# Miscel.net
KiCad netlist of a schematic drawn in EasyEDA
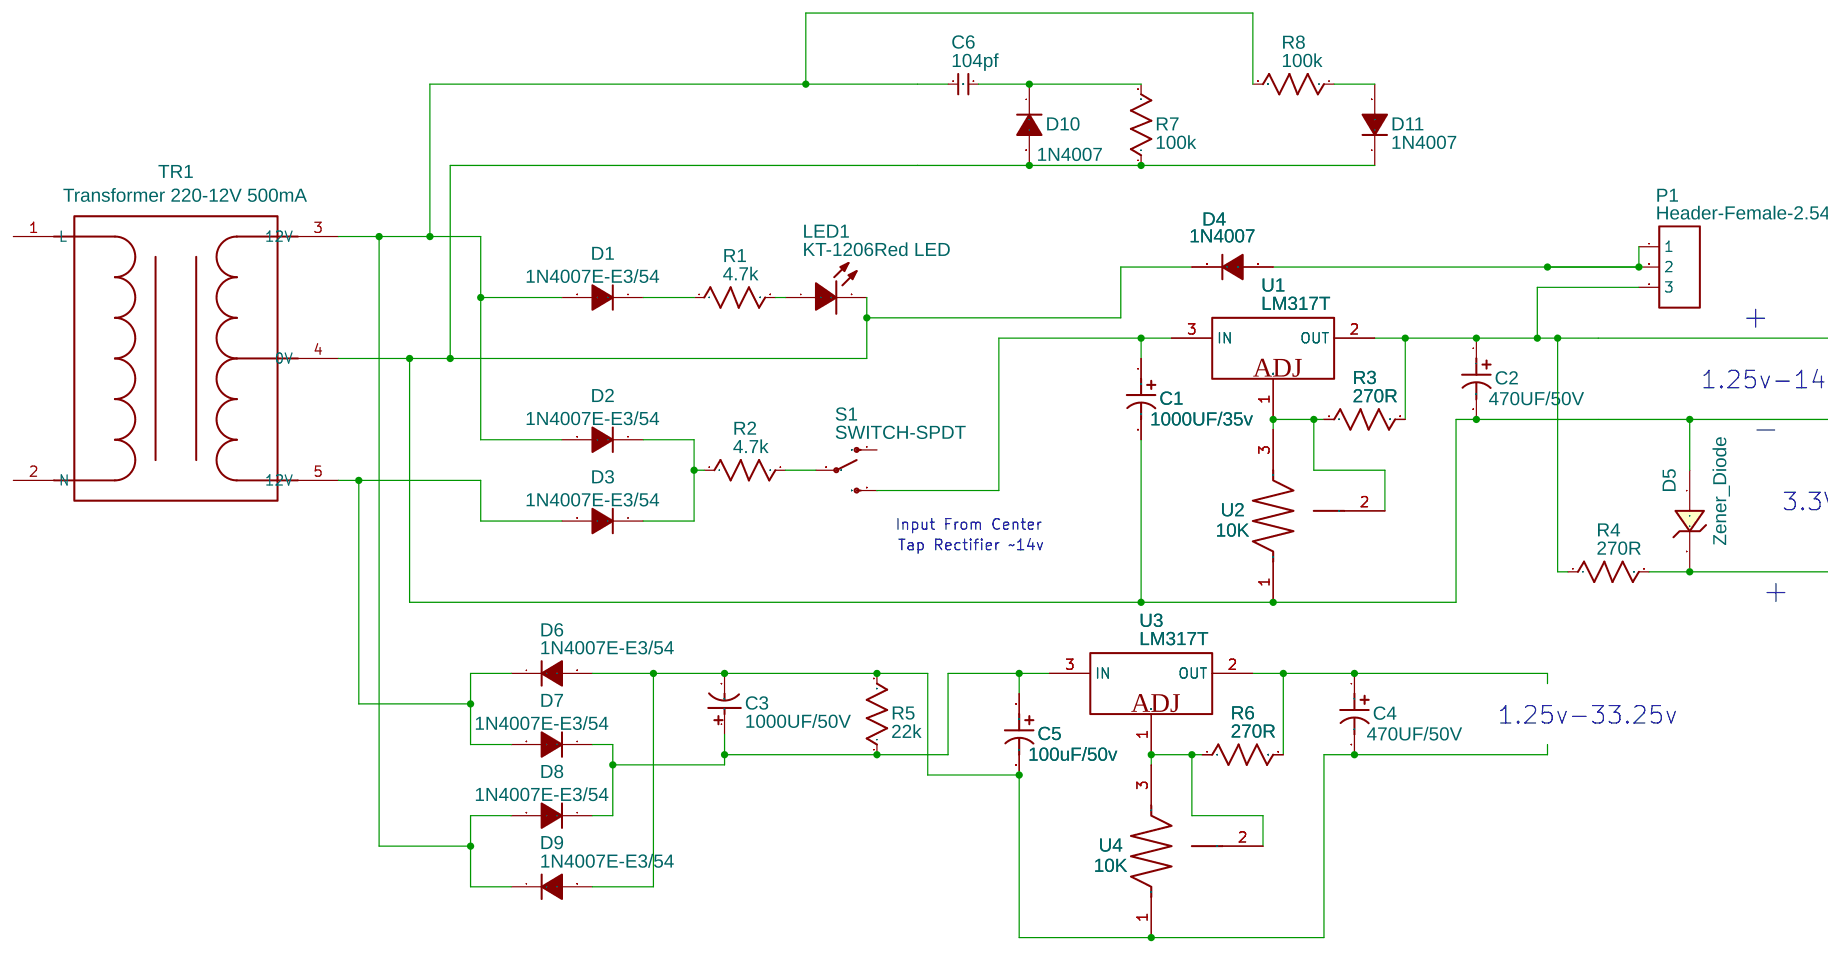
[diagram p0: schematic sheet]

(export (version "E")
  (design (tool "Eeschema 10.0.6"))
  (components
    (comp (ref "C1")
      (value "1000UF/35v")
      (fields
        (field (name "BOM_Manufacturer Part") "100uF/50V")
        (field (name "BOM_Supplier Part") "C9900004739")
      )
      (libsource (lib "") (part "100UF/50V"))
    )
    (comp (ref "C2")
      (value "470UF/50V")
      (fields
        (field (name "BOM_Manufacturer Part") "470uF/50V-10x20")
        (field (name "BOM_Supplier Part") "C9900005233")
      )
      (libsource (lib "") (part "470UF/50V-10X20"))
    )
    (comp (ref "C3")
      (value "1000UF/50V")
      (fields
        (field (name "BOM_Manufacturer Part") "1000uF/50V")
        (field (name "BOM_Supplier Part") "C9900023728")
      )
      (libsource (lib "") (part "1000UF/50V"))
    )
    (comp (ref "C4")
      (value "470UF/50V")
      (fields
        (field (name "BOM_Manufacturer Part") "470uF/50V-10x20")
        (field (name "BOM_Supplier Part") "C9900005233")
      )
      (libsource (lib "") (part "470UF/50V-10X20"))
    )
    (comp (ref "C5")
      (value "100uF/50v")
      (fields
        (field (name "BOM_Manufacturer Part") "100uF/50V")
        (field (name "BOM_Supplier Part") "C9900004739")
      )
      (libsource (lib "") (part "100UF/50V"))
    )
    (comp (ref "C6") (value "104pf") (libsource (lib "") (part "104pf")))
    (comp (ref "D1")
      (value "1N4007E-E3/54")
      (fields (field (name "BOM_Supplier Part") "C144970"))
      (libsource (lib "") (part "1N4007E-E3/54"))
    )
    (comp (ref "D2")
      (value "1N4007E-E3/54")
      (fields (field (name "BOM_Supplier Part") "C144970"))
      (libsource (lib "") (part "1N4007E-E3/54"))
    )
    (comp (ref "D3")
      (value "1N4007E-E3/54")
      (fields (field (name "BOM_Supplier Part") "C144970"))
      (libsource (lib "") (part "1N4007E-E3/54"))
    )
    (comp (ref "D4")
      (value "1N4007")
      (fields
        (field (name "BOM_Manufacturer Part") "1N4007E-E3/54")
        (field (name "BOM_Supplier Part") "C144970")
      )
      (libsource (lib "") (part "1N4007E-E3/54_2"))
    )
    (comp (ref "D5") (value "Zener_Diode") (libsource (lib "") (part "Zener_Diode")))
    (comp (ref "D6")
      (value "1N4007E-E3/54")
      (fields (field (name "BOM_Supplier Part") "C144970"))
      (libsource (lib "") (part "1N4007E-E3/54_2"))
    )
    (comp (ref "D7")
      (value "1N4007E-E3/54")
      (fields (field (name "BOM_Supplier Part") "C144970"))
      (libsource (lib "") (part "1N4007E-E3/54"))
    )
    (comp (ref "D8")
      (value "1N4007E-E3/54")
      (fields (field (name "BOM_Supplier Part") "C144970"))
      (libsource (lib "") (part "1N4007E-E3/54"))
    )
    (comp (ref "D9")
      (value "1N4007E-E3/54")
      (fields (field (name "BOM_Supplier Part") "C144970"))
      (libsource (lib "") (part "1N4007E-E3/54_2"))
    )
    (comp (ref "D10")
      (value "1N4007")
      (fields
        (field (name "BOM_Manufacturer Part") "1N4007E-E3/54")
        (field (name "BOM_Supplier Part") "C144970")
      )
      (libsource (lib "") (part "1N4007E-E3/54_3"))
    )
    (comp (ref "D11")
      (value "1N4007")
      (fields
        (field (name "BOM_Manufacturer Part") "1N4007E-E3/54")
        (field (name "BOM_Supplier Part") "C144970")
      )
      (libsource (lib "") (part "1N4007E-E3/54_1"))
    )
    (comp (ref "LED1")
      (value "KT-1206Red LED")
      (fields (field (name "BOM_Supplier Part") "C49018"))
      (libsource (lib "") (part "KT-1206Red LED"))
    )
    (comp (ref "P1")
      (value "Header-Female-2.54_1x3")
      (fields
        (field (name "BOM_Manufacturer Part") "2.54-1*3P母")
        (field (name "BOM_Supplier Part") "C146243")
      )
      (libsource (lib "") (part "Header-Female-2.54_1x3"))
    )
    (comp (ref "R1") (value "4.7k") (libsource (lib "") (part "R_0603_US")))
    (comp (ref "R2") (value "4.7k") (libsource (lib "") (part "R_0603_US")))
    (comp (ref "R3") (value "270R") (libsource (lib "") (part "R_0603_US")))
    (comp (ref "R4") (value "270R") (libsource (lib "") (part "R_0603_US")))
    (comp (ref "R5") (value "22k") (libsource (lib "") (part "R_0603_US_1")))
    (comp (ref "R6") (value "270R") (libsource (lib "") (part "R_0603_US")))
    (comp (ref "R7") (value "100k") (libsource (lib "") (part "R_0603_US_1")))
    (comp (ref "R8") (value "100k") (libsource (lib "") (part "R_0603_US_2")))
    (comp (ref "S1") (value "SWITCH-SPDT") (libsource (lib "") (part "SWITCH-SPDT")))
    (comp (ref "TR1")
      (value "Transformer 220-12V 500mA")
      (libsource (lib "") (part "Transformer 220-12V 500mA"))
    )
    (comp (ref "U1") (value "LM317T") (libsource (lib "") (part "LM317T")))
    (comp (ref "U2") (value "10K") (libsource (lib "") (part "POTENTIOMETER")))
    (comp (ref "U3") (value "LM317T") (libsource (lib "") (part "LM317T")))
    (comp (ref "U4") (value "10K") (libsource (lib "") (part "POTENTIOMETER")))
  )
  (nets
    (net (code "1") (name "Net-(D1-A)") (class "Default")
      (node (ref "C6") (pin "1") (pinfunction "1_1") (pintype "unspecified"))
      (node (ref "D1") (pin "2") (pinfunction "A_2") (pintype "unspecified"))
      (node (ref "D2") (pin "2") (pinfunction "A_2") (pintype "unspecified"))
      (node (ref "D8") (pin "2") (pinfunction "A_2") (pintype "unspecified"))
      (node (ref "D9") (pin "1") (pinfunction "K_1") (pintype "unspecified"))
      (node (ref "R8") (pin "2") (pinfunction "2_2") (pintype "unspecified"))
      (node (ref "TR1") (pin "3") (pinfunction "12V_3") (pintype "unspecified"))
    )
    (net (code "2") (name "Net-(D1-K)") (class "Default")
      (node (ref "D1") (pin "1") (pinfunction "K_1") (pintype "unspecified"))
      (node (ref "R1") (pin "1") (pinfunction "1_1") (pintype "unspecified"))
    )
    (net (code "3") (name "Net-(D2-K)") (class "Default")
      (node (ref "D2") (pin "1") (pinfunction "K_1") (pintype "unspecified"))
      (node (ref "D3") (pin "1") (pinfunction "K_1") (pintype "unspecified"))
      (node (ref "R2") (pin "1") (pinfunction "1_1") (pintype "unspecified"))
    )
    (net (code "4") (name "Net-(D3-A)") (class "Default")
      (node (ref "D3") (pin "2") (pinfunction "A_2") (pintype "unspecified"))
      (node (ref "D6") (pin "1") (pinfunction "K_1") (pintype "unspecified"))
      (node (ref "D7") (pin "2") (pinfunction "A_2") (pintype "unspecified"))
      (node (ref "TR1") (pin "5") (pinfunction "12V_5") (pintype "unspecified"))
    )
    (net (code "5") (name "Net-(D4-A)") (class "Default")
      (node (ref "D4") (pin "2") (pinfunction "A_2") (pintype "unspecified"))
      (node (ref "P1") (pin "1") (pinfunction "1_1") (pintype "input"))
      (node (ref "P1") (pin "2") (pinfunction "2_2") (pintype "input"))
    )
    (net (code "6") (name "Net-(D5-K)") (class "Default")
      (node (ref "D5") (pin "2") (pinfunction "K_2") (pintype "unspecified"))
      (node (ref "R4") (pin "2") (pinfunction "2_2") (pintype "unspecified"))
    )
    (net (code "7") (name "Net-(D6-A)") (class "Default")
      (node (ref "C3") (pin "2") (pinfunction "2_2") (pintype "input"))
      (node (ref "C4") (pin "2") (pinfunction "2_2") (pintype "input"))
      (node (ref "C5") (pin "2") (pinfunction "2_2") (pintype "input"))
      (node (ref "D6") (pin "2") (pinfunction "A_2") (pintype "unspecified"))
      (node (ref "D9") (pin "2") (pinfunction "A_2") (pintype "unspecified"))
      (node (ref "R5") (pin "2") (pinfunction "2_2") (pintype "unspecified"))
      (node (ref "U4") (pin "1") (pinfunction "1_1") (pintype "unspecified"))
    )
    (net (code "8") (name "Net-(D7-K)") (class "Default")
      (node (ref "C3") (pin "1") (pinfunction "1_1") (pintype "input"))
      (node (ref "C5") (pin "1") (pinfunction "1_1") (pintype "input"))
      (node (ref "D7") (pin "1") (pinfunction "K_1") (pintype "unspecified"))
      (node (ref "D8") (pin "1") (pinfunction "K_1") (pintype "unspecified"))
      (node (ref "R5") (pin "1") (pinfunction "1_1") (pintype "unspecified"))
      (node (ref "U3") (pin "3") (pinfunction "IN_3") (pintype "passive"))
    )
    (net (code "9") (name "Net-(D10-A)") (class "Default")
      (node (ref "C1") (pin "2") (pinfunction "2_2") (pintype "input"))
      (node (ref "C2") (pin "2") (pinfunction "2_2") (pintype "input"))
      (node (ref "D10") (pin "2") (pinfunction "A_2") (pintype "unspecified"))
      (node (ref "D11") (pin "1") (pinfunction "K_1") (pintype "unspecified"))
      (node (ref "D4") (pin "1") (pinfunction "K_1") (pintype "unspecified"))
      (node (ref "D5") (pin "1") (pinfunction "A_1") (pintype "unspecified"))
      (node (ref "LED1") (pin "2") (pinfunction "K_2") (pintype "unspecified"))
      (node (ref "R7") (pin "1") (pinfunction "1_1") (pintype "unspecified"))
      (node (ref "TR1") (pin "4") (pinfunction "0V_4") (pintype "unspecified"))
      (node (ref "U2") (pin "1") (pinfunction "1_1") (pintype "unspecified"))
    )
    (net (code "10") (name "Net-(D10-K)") (class "Default")
      (node (ref "C6") (pin "2") (pinfunction "2_2") (pintype "unspecified"))
      (node (ref "D10") (pin "1") (pinfunction "K_1") (pintype "unspecified"))
      (node (ref "R7") (pin "2") (pinfunction "2_2") (pintype "unspecified"))
    )
    (net (code "11") (name "Net-(D11-A)") (class "Default")
      (node (ref "D11") (pin "2") (pinfunction "A_2") (pintype "unspecified"))
      (node (ref "R8") (pin "1") (pinfunction "1_1") (pintype "unspecified"))
    )
    (net (code "12") (name "Net-(LED1-A)") (class "Default")
      (node (ref "LED1") (pin "1") (pinfunction "A_1") (pintype "unspecified"))
      (node (ref "R1") (pin "2") (pinfunction "2_2") (pintype "unspecified"))
    )
    (net (code "13") (name "Net-(S1-P)") (class "Default")
      (node (ref "R2") (pin "2") (pinfunction "2_2") (pintype "unspecified"))
      (node (ref "S1") (pin "2") (pinfunction "P_2") (pintype "unspecified"))
    )
    (net (code "14") (name "Net-(S1-S)") (class "Default")
      (node (ref "C1") (pin "1") (pinfunction "1_1") (pintype "input"))
      (node (ref "S1") (pin "3") (pinfunction "S_3") (pintype "unspecified"))
      (node (ref "U1") (pin "3") (pinfunction "IN_3") (pintype "passive"))
    )
    (net (code "15") (name "Net-(U1-ADJ)") (class "Default")
      (node (ref "R3") (pin "1") (pinfunction "1_1") (pintype "unspecified"))
      (node (ref "U1") (pin "1") (pinfunction "ADJ_1") (pintype "unspecified"))
      (node (ref "U2") (pin "2") (pinfunction "2_2") (pintype "unspecified"))
      (node (ref "U2") (pin "3") (pinfunction "3_3") (pintype "unspecified"))
    )
    (net (code "16") (name "Net-(U1-OUT)") (class "Default")
      (node (ref "C2") (pin "1") (pinfunction "1_1") (pintype "input"))
      (node (ref "P1") (pin "3") (pinfunction "3_3") (pintype "input"))
      (node (ref "R3") (pin "2") (pinfunction "2_2") (pintype "unspecified"))
      (node (ref "R4") (pin "1") (pinfunction "1_1") (pintype "unspecified"))
      (node (ref "U1") (pin "2") (pinfunction "OUT_2") (pintype "passive"))
    )
    (net (code "17") (name "Net-(U3-ADJ)") (class "Default")
      (node (ref "R6") (pin "1") (pinfunction "1_1") (pintype "unspecified"))
      (node (ref "U3") (pin "1") (pinfunction "ADJ_1") (pintype "unspecified"))
      (node (ref "U4") (pin "2") (pinfunction "2_2") (pintype "unspecified"))
      (node (ref "U4") (pin "3") (pinfunction "3_3") (pintype "unspecified"))
    )
    (net (code "18") (name "Net-(U3-OUT)") (class "Default")
      (node (ref "C4") (pin "1") (pinfunction "1_1") (pintype "input"))
      (node (ref "R6") (pin "2") (pinfunction "2_2") (pintype "unspecified"))
      (node (ref "U3") (pin "2") (pinfunction "OUT_2") (pintype "passive"))
    )
    (net (code "19") (name "unconnected-(S1-O-Pad1)") (class "Default")
      (node (ref "S1") (pin "1") (pinfunction "O_1") (pintype "unspecified"))
    )
    (net (code "20") (name "unconnected-(TR1-L-Pad1)") (class "Default")
      (node (ref "TR1") (pin "1") (pinfunction "L_1") (pintype "unspecified"))
    )
    (net (code "21") (name "unconnected-(TR1-N-Pad2)") (class "Default")
      (node (ref "TR1") (pin "2") (pinfunction "N_2") (pintype "unspecified"))
    )
  )
)
